# pi1541.net
KiCad netlist of a schematic drawn in EAGLE
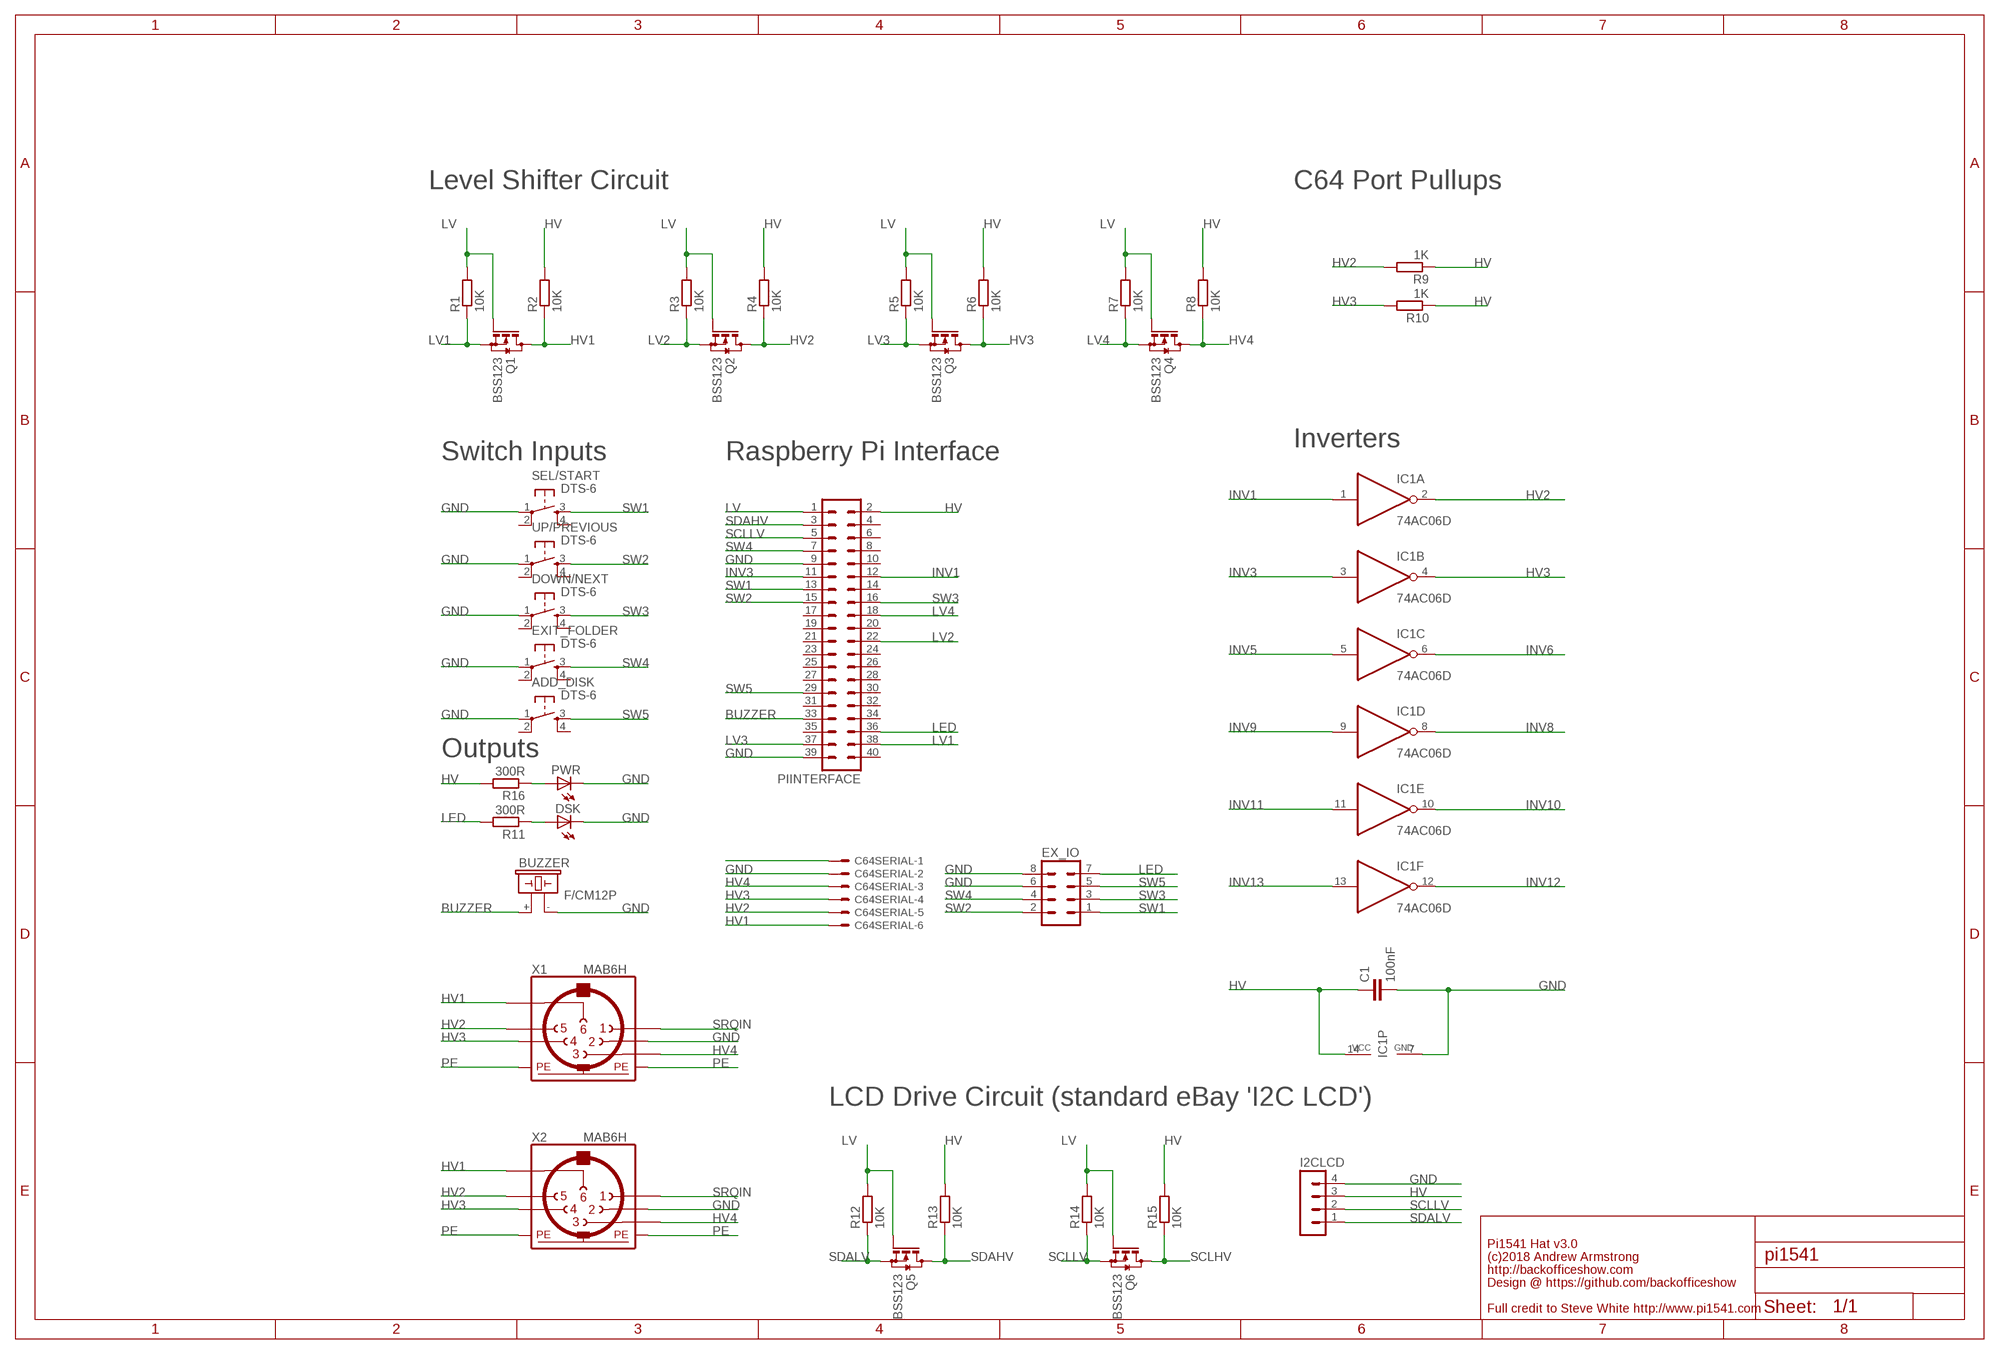
[diagram p0: schematic, sheet 1]

(export (version "E")
  (design (tool "Eeschema 10.0.6"))
  (components
    (comp (ref "ADD_DISK")
      (value "DTS-6")
      (footprint "eagle-import:DTS-6")
      (libsource (lib "eagle-import") (part "DTS-6"))
    )
    (comp (ref "BUZZER")
      (value "F/CM12P")
      (footprint "eagle-import:F_CM12P")
      (libsource (lib "eagle-import") (part "F/CM12P"))
    )
    (comp (ref "C1")
      (value "100nF")
      (footprint "eagle-import:C0805")
      (libsource (lib "eagle-import") (part "C-EUC0805"))
    )
    (comp (ref "C64SERIAL")
      (value "22-23-2061")
      (footprint "eagle-import:22-23-2061")
      (libsource (lib "eagle-import") (part "22-23-2061"))
    )
    (comp (ref "DOWN/NEXT")
      (value "DTS-6")
      (footprint "eagle-import:DTS-6")
      (libsource (lib "eagle-import") (part "DTS-6"))
    )
    (comp (ref "DSK")
      (value "LEDCHIPLED_0805")
      (footprint "eagle-import:CHIPLED_0805")
      (libsource (lib "eagle-import") (part "LEDCHIPLED_0805"))
    )
    (comp (ref "EXIT_FOLDER")
      (value "DTS-6")
      (footprint "eagle-import:DTS-6")
      (libsource (lib "eagle-import") (part "DTS-6"))
    )
    (comp (ref "EX_IO")
      (value "MA04-2")
      (footprint "eagle-import:MA04-2")
      (libsource (lib "eagle-import") (part "MA04-2"))
    )
    (comp (ref "I2CLCD")
      (value "MA04-1")
      (footprint "eagle-import:MA04-1")
      (libsource (lib "eagle-import") (part "MA04-1"))
    )
    (comp (ref "IC1")
      (value "74AC06D")
      (footprint "eagle-import:SO14")
      (libsource (lib "eagle-import") (part "7406DAC"))
    )
    (comp (ref "PIINTERFACE")
      (value "MA20-2")
      (footprint "eagle-import:MA20-2")
      (libsource (lib "eagle-import") (part "MA20-2"))
    )
    (comp (ref "PWR")
      (value "LEDCHIPLED_0805")
      (footprint "eagle-import:CHIPLED_0805")
      (libsource (lib "eagle-import") (part "LEDCHIPLED_0805"))
    )
    (comp (ref "Q1")
      (value "BSS123")
      (footprint "eagle-import:SOT23")
      (libsource (lib "eagle-import") (part "BSS123"))
    )
    (comp (ref "Q2")
      (value "BSS123")
      (footprint "eagle-import:SOT23")
      (libsource (lib "eagle-import") (part "BSS123"))
    )
    (comp (ref "Q3")
      (value "BSS123")
      (footprint "eagle-import:SOT23")
      (libsource (lib "eagle-import") (part "BSS123"))
    )
    (comp (ref "Q4")
      (value "BSS123")
      (footprint "eagle-import:SOT23")
      (libsource (lib "eagle-import") (part "BSS123"))
    )
    (comp (ref "Q5")
      (value "BSS123")
      (footprint "eagle-import:SOT23")
      (libsource (lib "eagle-import") (part "BSS123"))
    )
    (comp (ref "Q6")
      (value "BSS123")
      (footprint "eagle-import:SOT23")
      (libsource (lib "eagle-import") (part "BSS123"))
    )
    (comp (ref "R1")
      (value "10K")
      (footprint "eagle-import:R0805")
      (libsource (lib "eagle-import") (part "R-EU_R0805"))
    )
    (comp (ref "R2")
      (value "10K")
      (footprint "eagle-import:R0805")
      (libsource (lib "eagle-import") (part "R-EU_R0805"))
    )
    (comp (ref "R3")
      (value "10K")
      (footprint "eagle-import:R0805")
      (libsource (lib "eagle-import") (part "R-EU_R0805"))
    )
    (comp (ref "R4")
      (value "10K")
      (footprint "eagle-import:R0805")
      (libsource (lib "eagle-import") (part "R-EU_R0805"))
    )
    (comp (ref "R5")
      (value "10K")
      (footprint "eagle-import:R0805")
      (libsource (lib "eagle-import") (part "R-EU_R0805"))
    )
    (comp (ref "R6")
      (value "10K")
      (footprint "eagle-import:R0805")
      (libsource (lib "eagle-import") (part "R-EU_R0805"))
    )
    (comp (ref "R7")
      (value "10K")
      (footprint "eagle-import:R0805")
      (libsource (lib "eagle-import") (part "R-EU_R0805"))
    )
    (comp (ref "R8")
      (value "10K")
      (footprint "eagle-import:R0805")
      (libsource (lib "eagle-import") (part "R-EU_R0805"))
    )
    (comp (ref "R9")
      (value "1K")
      (footprint "eagle-import:R0805")
      (libsource (lib "eagle-import") (part "R-EU_R0805"))
    )
    (comp (ref "R10")
      (value "1K")
      (footprint "eagle-import:R0805")
      (libsource (lib "eagle-import") (part "R-EU_R0805"))
    )
    (comp (ref "R11")
      (value "300R")
      (footprint "eagle-import:R0805")
      (libsource (lib "eagle-import") (part "R-EU_R0805"))
    )
    (comp (ref "R12")
      (value "10K")
      (footprint "eagle-import:R0805")
      (libsource (lib "eagle-import") (part "R-EU_R0805"))
    )
    (comp (ref "R13")
      (value "10K")
      (footprint "eagle-import:R0805")
      (libsource (lib "eagle-import") (part "R-EU_R0805"))
    )
    (comp (ref "R14")
      (value "10K")
      (footprint "eagle-import:R0805")
      (libsource (lib "eagle-import") (part "R-EU_R0805"))
    )
    (comp (ref "R15")
      (value "10K")
      (footprint "eagle-import:R0805")
      (libsource (lib "eagle-import") (part "R-EU_R0805"))
    )
    (comp (ref "R16")
      (value "300R")
      (footprint "eagle-import:R0805")
      (libsource (lib "eagle-import") (part "R-EU_R0805"))
    )
    (comp (ref "SEL/START")
      (value "DTS-6")
      (footprint "eagle-import:DTS-6")
      (libsource (lib "eagle-import") (part "DTS-6"))
    )
    (comp (ref "UP/PREVIOUS")
      (value "DTS-6")
      (footprint "eagle-import:DTS-6")
      (libsource (lib "eagle-import") (part "DTS-6"))
    )
    (comp (ref "X1")
      (value "MAB6H")
      (footprint "eagle-import:MAB6H")
      (libsource (lib "eagle-import") (part "MAB6H"))
    )
    (comp (ref "X2")
      (value "MAB6H")
      (footprint "eagle-import:MAB6H")
      (libsource (lib "eagle-import") (part "MAB6H"))
    )
  )
  (nets
    (net (code "1") (name "/BUZZER") (class "Default")
      (node (ref "BUZZER") (pin "+") (pinfunction "1_+") (pintype "passive"))
      (node (ref "PIINTERFACE") (pin "33") (pinfunction "33_33") (pintype "passive"))
    )
    (net (code "2") (name "/GND") (class "Default")
      (node (ref "ADD_DISK") (pin "1") (pinfunction "1_1") (pintype "passive"))
      (node (ref "BUZZER") (pin "-") (pinfunction "2_-") (pintype "passive"))
      (node (ref "C1") (pin "2") (pinfunction "2_2") (pintype "passive"))
      (node (ref "C64SERIAL") (pin "2") (pinfunction "S_2") (pintype "passive"))
      (node (ref "DOWN/NEXT") (pin "1") (pinfunction "1_1") (pintype "passive"))
      (node (ref "DSK") (pin "C") (pinfunction "C_C") (pintype "passive"))
      (node (ref "EXIT_FOLDER") (pin "1") (pinfunction "1_1") (pintype "passive"))
      (node (ref "EX_IO") (pin "6") (pinfunction "6_6") (pintype "passive"))
      (node (ref "EX_IO") (pin "8") (pinfunction "8_8") (pintype "passive"))
      (node (ref "I2CLCD") (pin "4") (pinfunction "4_4") (pintype "passive"))
      (node (ref "IC1") (pin "7") (pinfunction "GND_7") (pintype "power_in"))
      (node (ref "PIINTERFACE") (pin "39") (pinfunction "39_39") (pintype "passive"))
      (node (ref "PIINTERFACE") (pin "9") (pinfunction "9_9") (pintype "passive"))
      (node (ref "PWR") (pin "C") (pinfunction "C_C") (pintype "passive"))
      (node (ref "SEL/START") (pin "1") (pinfunction "1_1") (pintype "passive"))
      (node (ref "UP/PREVIOUS") (pin "1") (pinfunction "1_1") (pintype "passive"))
      (node (ref "X1") (pin "2") (pinfunction "2_2") (pintype "passive"))
      (node (ref "X2") (pin "2") (pinfunction "2_2") (pintype "passive"))
    )
    (net (code "3") (name "/HV") (class "Default")
      (node (ref "C1") (pin "1") (pinfunction "1_1") (pintype "passive"))
      (node (ref "I2CLCD") (pin "3") (pinfunction "3_3") (pintype "passive"))
      (node (ref "IC1") (pin "14") (pinfunction "VCC_14") (pintype "power_in"))
      (node (ref "PIINTERFACE") (pin "2") (pinfunction "2_2") (pintype "passive"))
      (node (ref "R10") (pin "1") (pinfunction "1_1") (pintype "passive"))
      (node (ref "R13") (pin "2") (pinfunction "2_2") (pintype "passive"))
      (node (ref "R15") (pin "2") (pinfunction "2_2") (pintype "passive"))
      (node (ref "R16") (pin "2") (pinfunction "2_2") (pintype "passive"))
      (node (ref "R2") (pin "2") (pinfunction "2_2") (pintype "passive"))
      (node (ref "R4") (pin "2") (pinfunction "2_2") (pintype "passive"))
      (node (ref "R6") (pin "2") (pinfunction "2_2") (pintype "passive"))
      (node (ref "R8") (pin "2") (pinfunction "2_2") (pintype "passive"))
      (node (ref "R9") (pin "1") (pinfunction "1_1") (pintype "passive"))
    )
    (net (code "4") (name "/HV1") (class "Default")
      (node (ref "C64SERIAL") (pin "6") (pinfunction "S_6") (pintype "passive"))
      (node (ref "Q1") (pin "3") (pinfunction "D_3") (pintype "passive"))
      (node (ref "R2") (pin "1") (pinfunction "1_1") (pintype "passive"))
      (node (ref "X1") (pin "6") (pinfunction "6_6") (pintype "passive"))
      (node (ref "X2") (pin "6") (pinfunction "6_6") (pintype "passive"))
    )
    (net (code "5") (name "/HV2") (class "Default")
      (node (ref "C64SERIAL") (pin "5") (pinfunction "S_5") (pintype "passive"))
      (node (ref "IC1") (pin "2") (pinfunction "O_2") (pintype "open_collector"))
      (node (ref "Q2") (pin "3") (pinfunction "D_3") (pintype "passive"))
      (node (ref "R4") (pin "1") (pinfunction "1_1") (pintype "passive"))
      (node (ref "R9") (pin "2") (pinfunction "2_2") (pintype "passive"))
      (node (ref "X1") (pin "5") (pinfunction "5_5") (pintype "passive"))
      (node (ref "X2") (pin "5") (pinfunction "5_5") (pintype "passive"))
    )
    (net (code "6") (name "/HV3") (class "Default")
      (node (ref "C64SERIAL") (pin "4") (pinfunction "S_4") (pintype "passive"))
      (node (ref "IC1") (pin "4") (pinfunction "O_4") (pintype "open_collector"))
      (node (ref "Q3") (pin "3") (pinfunction "D_3") (pintype "passive"))
      (node (ref "R10") (pin "2") (pinfunction "2_2") (pintype "passive"))
      (node (ref "R6") (pin "1") (pinfunction "1_1") (pintype "passive"))
      (node (ref "X1") (pin "4") (pinfunction "4_4") (pintype "passive"))
      (node (ref "X2") (pin "4") (pinfunction "4_4") (pintype "passive"))
    )
    (net (code "7") (name "/HV4") (class "Default")
      (node (ref "C64SERIAL") (pin "3") (pinfunction "S_3") (pintype "passive"))
      (node (ref "Q4") (pin "3") (pinfunction "D_3") (pintype "passive"))
      (node (ref "R8") (pin "1") (pinfunction "1_1") (pintype "passive"))
      (node (ref "X1") (pin "3") (pinfunction "3_3") (pintype "passive"))
      (node (ref "X2") (pin "3") (pinfunction "3_3") (pintype "passive"))
    )
    (net (code "8") (name "/INV1") (class "Default")
      (node (ref "IC1") (pin "1") (pinfunction "I_1") (pintype "input"))
      (node (ref "PIINTERFACE") (pin "12") (pinfunction "12_12") (pintype "passive"))
    )
    (net (code "9") (name "/INV3") (class "Default")
      (node (ref "IC1") (pin "3") (pinfunction "I_3") (pintype "input"))
      (node (ref "PIINTERFACE") (pin "11") (pinfunction "11_11") (pintype "passive"))
    )
    (net (code "10") (name "/INV5") (class "Default")
      (node (ref "IC1") (pin "5") (pinfunction "I_5") (pintype "input"))
    )
    (net (code "11") (name "/INV6") (class "Default")
      (node (ref "IC1") (pin "6") (pinfunction "O_6") (pintype "open_collector"))
    )
    (net (code "12") (name "/INV8") (class "Default")
      (node (ref "IC1") (pin "8") (pinfunction "O_8") (pintype "open_collector"))
    )
    (net (code "13") (name "/INV9") (class "Default")
      (node (ref "IC1") (pin "9") (pinfunction "I_9") (pintype "input"))
    )
    (net (code "14") (name "/INV10") (class "Default")
      (node (ref "IC1") (pin "10") (pinfunction "O_10") (pintype "open_collector"))
    )
    (net (code "15") (name "/INV11") (class "Default")
      (node (ref "IC1") (pin "11") (pinfunction "I_11") (pintype "input"))
    )
    (net (code "16") (name "/INV12") (class "Default")
      (node (ref "IC1") (pin "12") (pinfunction "O_12") (pintype "open_collector"))
    )
    (net (code "17") (name "/INV13") (class "Default")
      (node (ref "IC1") (pin "13") (pinfunction "I_13") (pintype "input"))
    )
    (net (code "18") (name "/LED") (class "Default")
      (node (ref "EX_IO") (pin "7") (pinfunction "7_7") (pintype "passive"))
      (node (ref "PIINTERFACE") (pin "36") (pinfunction "36_36") (pintype "passive"))
      (node (ref "R11") (pin "2") (pinfunction "2_2") (pintype "passive"))
    )
    (net (code "19") (name "/LV") (class "Default")
      (node (ref "PIINTERFACE") (pin "1") (pinfunction "1_1") (pintype "passive"))
      (node (ref "Q1") (pin "1") (pinfunction "G_1") (pintype "passive"))
      (node (ref "Q2") (pin "1") (pinfunction "G_1") (pintype "passive"))
      (node (ref "Q3") (pin "1") (pinfunction "G_1") (pintype "passive"))
      (node (ref "Q4") (pin "1") (pinfunction "G_1") (pintype "passive"))
      (node (ref "Q5") (pin "1") (pinfunction "G_1") (pintype "passive"))
      (node (ref "Q6") (pin "1") (pinfunction "G_1") (pintype "passive"))
      (node (ref "R1") (pin "2") (pinfunction "2_2") (pintype "passive"))
      (node (ref "R12") (pin "2") (pinfunction "2_2") (pintype "passive"))
      (node (ref "R14") (pin "2") (pinfunction "2_2") (pintype "passive"))
      (node (ref "R3") (pin "2") (pinfunction "2_2") (pintype "passive"))
      (node (ref "R5") (pin "2") (pinfunction "2_2") (pintype "passive"))
      (node (ref "R7") (pin "2") (pinfunction "2_2") (pintype "passive"))
    )
    (net (code "20") (name "/LV1") (class "Default")
      (node (ref "PIINTERFACE") (pin "38") (pinfunction "38_38") (pintype "passive"))
      (node (ref "Q1") (pin "2") (pinfunction "S_2") (pintype "passive"))
      (node (ref "R1") (pin "1") (pinfunction "1_1") (pintype "passive"))
    )
    (net (code "21") (name "/LV2") (class "Default")
      (node (ref "PIINTERFACE") (pin "22") (pinfunction "22_22") (pintype "passive"))
      (node (ref "Q2") (pin "2") (pinfunction "S_2") (pintype "passive"))
      (node (ref "R3") (pin "1") (pinfunction "1_1") (pintype "passive"))
    )
    (net (code "22") (name "/LV3") (class "Default")
      (node (ref "PIINTERFACE") (pin "37") (pinfunction "37_37") (pintype "passive"))
      (node (ref "Q3") (pin "2") (pinfunction "S_2") (pintype "passive"))
      (node (ref "R5") (pin "1") (pinfunction "1_1") (pintype "passive"))
    )
    (net (code "23") (name "/LV4") (class "Default")
      (node (ref "PIINTERFACE") (pin "18") (pinfunction "18_18") (pintype "passive"))
      (node (ref "Q4") (pin "2") (pinfunction "S_2") (pintype "passive"))
      (node (ref "R7") (pin "1") (pinfunction "1_1") (pintype "passive"))
    )
    (net (code "24") (name "/PE") (class "Default")
      (node (ref "X1") (pin "PE") (pinfunction "PE_PE") (pintype "power_in"))
      (node (ref "X1") (pin "PE@") (pinfunction "PE_PE@") (pintype "power_in"))
      (node (ref "X2") (pin "PE") (pinfunction "PE_PE") (pintype "power_in"))
      (node (ref "X2") (pin "PE@") (pinfunction "PE_PE@") (pintype "power_in"))
    )
    (net (code "25") (name "/SCLHV") (class "Default")
      (node (ref "Q6") (pin "3") (pinfunction "D_3") (pintype "passive"))
      (node (ref "R15") (pin "1") (pinfunction "1_1") (pintype "passive"))
    )
    (net (code "26") (name "/SCLLV") (class "Default")
      (node (ref "I2CLCD") (pin "2") (pinfunction "2_2") (pintype "passive"))
      (node (ref "PIINTERFACE") (pin "5") (pinfunction "5_5") (pintype "passive"))
      (node (ref "Q6") (pin "2") (pinfunction "S_2") (pintype "passive"))
      (node (ref "R14") (pin "1") (pinfunction "1_1") (pintype "passive"))
    )
    (net (code "27") (name "/SDAHV") (class "Default")
      (node (ref "PIINTERFACE") (pin "3") (pinfunction "3_3") (pintype "passive"))
      (node (ref "Q5") (pin "3") (pinfunction "D_3") (pintype "passive"))
      (node (ref "R13") (pin "1") (pinfunction "1_1") (pintype "passive"))
    )
    (net (code "28") (name "/SDALV") (class "Default")
      (node (ref "I2CLCD") (pin "1") (pinfunction "1_1") (pintype "passive"))
      (node (ref "Q5") (pin "2") (pinfunction "S_2") (pintype "passive"))
      (node (ref "R12") (pin "1") (pinfunction "1_1") (pintype "passive"))
    )
    (net (code "29") (name "/SRQIN") (class "Default")
      (node (ref "X1") (pin "1") (pinfunction "1_1") (pintype "passive"))
      (node (ref "X2") (pin "1") (pinfunction "1_1") (pintype "passive"))
    )
    (net (code "30") (name "/SW1") (class "Default")
      (node (ref "EX_IO") (pin "1") (pinfunction "1_1") (pintype "passive"))
      (node (ref "PIINTERFACE") (pin "13") (pinfunction "13_13") (pintype "passive"))
      (node (ref "SEL/START") (pin "3") (pinfunction "3_3") (pintype "passive"))
    )
    (net (code "31") (name "/SW2") (class "Default")
      (node (ref "EX_IO") (pin "2") (pinfunction "2_2") (pintype "passive"))
      (node (ref "PIINTERFACE") (pin "15") (pinfunction "15_15") (pintype "passive"))
      (node (ref "UP/PREVIOUS") (pin "3") (pinfunction "3_3") (pintype "passive"))
    )
    (net (code "32") (name "/SW3") (class "Default")
      (node (ref "DOWN/NEXT") (pin "3") (pinfunction "3_3") (pintype "passive"))
      (node (ref "EX_IO") (pin "3") (pinfunction "3_3") (pintype "passive"))
      (node (ref "PIINTERFACE") (pin "16") (pinfunction "16_16") (pintype "passive"))
    )
    (net (code "33") (name "/SW4") (class "Default")
      (node (ref "EXIT_FOLDER") (pin "3") (pinfunction "3_3") (pintype "passive"))
      (node (ref "EX_IO") (pin "4") (pinfunction "4_4") (pintype "passive"))
      (node (ref "PIINTERFACE") (pin "7") (pinfunction "7_7") (pintype "passive"))
    )
    (net (code "34") (name "/SW5") (class "Default")
      (node (ref "ADD_DISK") (pin "3") (pinfunction "3_3") (pintype "passive"))
      (node (ref "EX_IO") (pin "5") (pinfunction "5_5") (pintype "passive"))
      (node (ref "PIINTERFACE") (pin "29") (pinfunction "29_29") (pintype "passive"))
    )
    (net (code "35") (name "Net-(DSK-PadA)") (class "Default")
      (node (ref "DSK") (pin "A") (pinfunction "A_A") (pintype "passive"))
      (node (ref "R11") (pin "1") (pinfunction "1_1") (pintype "passive"))
    )
    (net (code "36") (name "Net-(PWR-PadA)") (class "Default")
      (node (ref "PWR") (pin "A") (pinfunction "A_A") (pintype "passive"))
      (node (ref "R16") (pin "1") (pinfunction "1_1") (pintype "passive"))
    )
    (net (code "37") (name "unconnected-(ADD_DISK-Pad2)") (class "Default")
      (node (ref "ADD_DISK") (pin "2") (pinfunction "2_2") (pintype "passive"))
    )
    (net (code "38") (name "unconnected-(ADD_DISK-Pad4)") (class "Default")
      (node (ref "ADD_DISK") (pin "4") (pinfunction "4_4") (pintype "passive"))
    )
    (net (code "39") (name "unconnected-(C64SERIALA-S-Pad1)") (class "Default")
      (node (ref "C64SERIAL") (pin "1") (pinfunction "S_1") (pintype "passive"))
    )
    (net (code "40") (name "unconnected-(DOWN/NEXT-Pad2)") (class "Default")
      (node (ref "DOWN/NEXT") (pin "2") (pinfunction "2_2") (pintype "passive"))
    )
    (net (code "41") (name "unconnected-(DOWN/NEXT-Pad4)") (class "Default")
      (node (ref "DOWN/NEXT") (pin "4") (pinfunction "4_4") (pintype "passive"))
    )
    (net (code "42") (name "unconnected-(EXIT_FOLDER-Pad2)") (class "Default")
      (node (ref "EXIT_FOLDER") (pin "2") (pinfunction "2_2") (pintype "passive"))
    )
    (net (code "43") (name "unconnected-(EXIT_FOLDER-Pad4)") (class "Default")
      (node (ref "EXIT_FOLDER") (pin "4") (pinfunction "4_4") (pintype "passive"))
    )
    (net (code "44") (name "unconnected-(PIINTERFACE-Pad4)") (class "Default")
      (node (ref "PIINTERFACE") (pin "4") (pinfunction "4_4") (pintype "passive"))
    )
    (net (code "45") (name "unconnected-(PIINTERFACE-Pad6)") (class "Default")
      (node (ref "PIINTERFACE") (pin "6") (pinfunction "6_6") (pintype "passive"))
    )
    (net (code "46") (name "unconnected-(PIINTERFACE-Pad8)") (class "Default")
      (node (ref "PIINTERFACE") (pin "8") (pinfunction "8_8") (pintype "passive"))
    )
    (net (code "47") (name "unconnected-(PIINTERFACE-Pad10)") (class "Default")
      (node (ref "PIINTERFACE") (pin "10") (pinfunction "10_10") (pintype "passive"))
    )
    (net (code "48") (name "unconnected-(PIINTERFACE-Pad14)") (class "Default")
      (node (ref "PIINTERFACE") (pin "14") (pinfunction "14_14") (pintype "passive"))
    )
    (net (code "49") (name "unconnected-(PIINTERFACE-Pad17)") (class "Default")
      (node (ref "PIINTERFACE") (pin "17") (pinfunction "17_17") (pintype "passive"))
    )
    (net (code "50") (name "unconnected-(PIINTERFACE-Pad19)") (class "Default")
      (node (ref "PIINTERFACE") (pin "19") (pinfunction "19_19") (pintype "passive"))
    )
    (net (code "51") (name "unconnected-(PIINTERFACE-Pad20)") (class "Default")
      (node (ref "PIINTERFACE") (pin "20") (pinfunction "20_20") (pintype "passive"))
    )
    (net (code "52") (name "unconnected-(PIINTERFACE-Pad21)") (class "Default")
      (node (ref "PIINTERFACE") (pin "21") (pinfunction "21_21") (pintype "passive"))
    )
    (net (code "53") (name "unconnected-(PIINTERFACE-Pad23)") (class "Default")
      (node (ref "PIINTERFACE") (pin "23") (pinfunction "23_23") (pintype "passive"))
    )
    (net (code "54") (name "unconnected-(PIINTERFACE-Pad24)") (class "Default")
      (node (ref "PIINTERFACE") (pin "24") (pinfunction "24_24") (pintype "passive"))
    )
    (net (code "55") (name "unconnected-(PIINTERFACE-Pad25)") (class "Default")
      (node (ref "PIINTERFACE") (pin "25") (pinfunction "25_25") (pintype "passive"))
    )
    (net (code "56") (name "unconnected-(PIINTERFACE-Pad26)") (class "Default")
      (node (ref "PIINTERFACE") (pin "26") (pinfunction "26_26") (pintype "passive"))
    )
    (net (code "57") (name "unconnected-(PIINTERFACE-Pad27)") (class "Default")
      (node (ref "PIINTERFACE") (pin "27") (pinfunction "27_27") (pintype "passive"))
    )
    (net (code "58") (name "unconnected-(PIINTERFACE-Pad28)") (class "Default")
      (node (ref "PIINTERFACE") (pin "28") (pinfunction "28_28") (pintype "passive"))
    )
    (net (code "59") (name "unconnected-(PIINTERFACE-Pad30)") (class "Default")
      (node (ref "PIINTERFACE") (pin "30") (pinfunction "30_30") (pintype "passive"))
    )
    (net (code "60") (name "unconnected-(PIINTERFACE-Pad31)") (class "Default")
      (node (ref "PIINTERFACE") (pin "31") (pinfunction "31_31") (pintype "passive"))
    )
    (net (code "61") (name "unconnected-(PIINTERFACE-Pad32)") (class "Default")
      (node (ref "PIINTERFACE") (pin "32") (pinfunction "32_32") (pintype "passive"))
    )
    (net (code "62") (name "unconnected-(PIINTERFACE-Pad34)") (class "Default")
      (node (ref "PIINTERFACE") (pin "34") (pinfunction "34_34") (pintype "passive"))
    )
    (net (code "63") (name "unconnected-(PIINTERFACE-Pad35)") (class "Default")
      (node (ref "PIINTERFACE") (pin "35") (pinfunction "35_35") (pintype "passive"))
    )
    (net (code "64") (name "unconnected-(PIINTERFACE-Pad40)") (class "Default")
      (node (ref "PIINTERFACE") (pin "40") (pinfunction "40_40") (pintype "passive"))
    )
    (net (code "65") (name "unconnected-(SEL/START-Pad2)") (class "Default")
      (node (ref "SEL/START") (pin "2") (pinfunction "2_2") (pintype "passive"))
    )
    (net (code "66") (name "unconnected-(SEL/START-Pad4)") (class "Default")
      (node (ref "SEL/START") (pin "4") (pinfunction "4_4") (pintype "passive"))
    )
    (net (code "67") (name "unconnected-(UP/PREVIOUS-Pad2)") (class "Default")
      (node (ref "UP/PREVIOUS") (pin "2") (pinfunction "2_2") (pintype "passive"))
    )
    (net (code "68") (name "unconnected-(UP/PREVIOUS-Pad4)") (class "Default")
      (node (ref "UP/PREVIOUS") (pin "4") (pinfunction "4_4") (pintype "passive"))
    )
  )
)
